# Battery_Management__rev3.net
KiCad netlist of a schematic drawn in Altium Designer
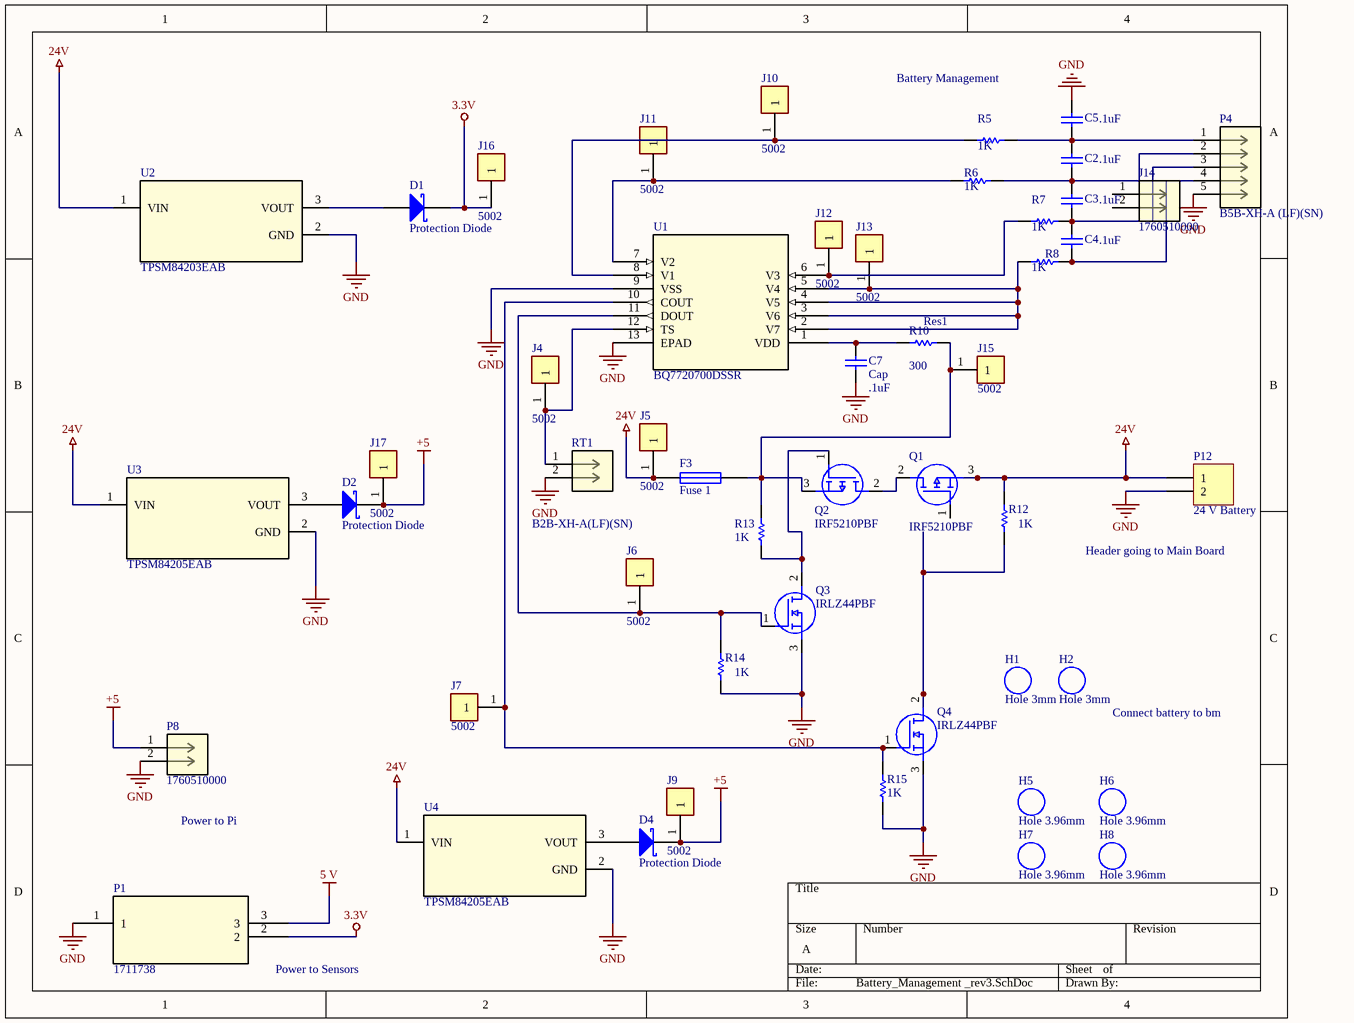
[diagram p0: Battery_Management _rev3.SchDoc]

(export (version "E")
  (design (tool "Eeschema 10.0.6"))
  (components
    (comp (ref "C2")
      (value ".1uF")
      (footprint "RAD-0.3")
      (description "Capacitor")
      (fields (field (name "Comment") "Cap") (field (name "PUBLISHER") "Altium Limited"))
      (libsource (lib "Miscellaneous Devices") (part "Cap"))
    )
    (comp (ref "C3")
      (value ".1uF")
      (footprint "RAD-0.3")
      (description "Capacitor")
      (fields (field (name "Comment") "Cap") (field (name "PUBLISHER") "Altium Limited"))
      (libsource (lib "Miscellaneous Devices") (part "Cap"))
    )
    (comp (ref "C4")
      (value ".1uF")
      (footprint "RAD-0.3")
      (description "Capacitor")
      (fields (field (name "Comment") "Cap") (field (name "PUBLISHER") "Altium Limited"))
      (libsource (lib "Miscellaneous Devices") (part "Cap"))
    )
    (comp (ref "C5")
      (value ".1uF")
      (footprint "RAD-0.3")
      (description "Capacitor")
      (fields (field (name "Comment") "Cap") (field (name "PUBLISHER") "Altium Limited"))
      (libsource (lib "Miscellaneous Devices") (part "Cap"))
    )
    (comp (ref "C7")
      (value "Cap")
      (footprint "RAD-0.3")
      (description "Capacitor")
      (fields (field (name "ALTIUM_VALUE") ".1uF") (field (name "PUBLISHER") "Altium Limited"))
      (libsource (lib "Miscellaneous Devices") (part "Cap"))
    )
    (comp (ref "D1")
      (value "Protection Diode")
      (footprint "TO-220AC")
      (description "Schottky Rectifier")
      (fields (field (name "PUBLISHER") "Altium Limited"))
      (libsource (lib "Miscellaneous Devices") (part "Diode 10TQ035"))
    )
    (comp (ref "D2")
      (value "Protection Diode")
      (footprint "TO-220AC")
      (description "Schottky Rectifier")
      (fields (field (name "PUBLISHER") "Altium Limited"))
      (libsource (lib "Miscellaneous Devices") (part "Diode 10TQ035"))
    )
    (comp (ref "D4")
      (value "Protection Diode")
      (footprint "TO-220AC")
      (description "Schottky Rectifier")
      (fields (field (name "PUBLISHER") "Altium Limited"))
      (libsource (lib "Miscellaneous Devices") (part "Diode 10TQ035"))
    )
    (comp (ref "F3")
      (value "Fuse 1")
      (footprint "PIN-W2/E2.8")
      (description "Fuse")
      (fields (field (name "PUBLISHER") "Altium Limited"))
      (libsource (lib "Miscellaneous Devices") (part "Fuse 1"))
    )
    (comp (ref "H1")
      (value "Hole 3mm")
      (footprint "Hole 3mm")
      (libsource (lib "ECE LIB 21") (part "Hole 3mm"))
    )
    (comp (ref "H2")
      (value "Hole 3mm")
      (footprint "Hole 3mm")
      (libsource (lib "ECE LIB 21") (part "Hole 3mm"))
    )
    (comp (ref "H5")
      (value "Hole 3.96mm")
      (footprint "Hole 3mm")
      (libsource (lib "ECE LIB 21") (part "Hole 3mm"))
    )
    (comp (ref "H6")
      (value "Hole 3.96mm")
      (footprint "Hole 3mm")
      (libsource (lib "ECE LIB 21") (part "Hole 3mm"))
    )
    (comp (ref "H7")
      (value "Hole 3.96mm")
      (footprint "Hole 3mm")
      (libsource (lib "ECE LIB 21") (part "Hole 3mm"))
    )
    (comp (ref "H8")
      (value "Hole 3.96mm")
      (footprint "Hole 3mm")
      (libsource (lib "ECE LIB 21") (part "Hole 3mm"))
    )
    (comp (ref "J4")
      (value "5002")
      (footprint "KEYSTONE_5002")
      (description "2.2ÂµH Shielded Wirewound Inductor 1.8A 66mOhm Max Nonstandard")
      (fields (field (name "MF") "Keystone Electronics"))
      (libsource (lib "") (part "5002_1"))
    )
    (comp (ref "J5")
      (value "5002")
      (footprint "KEYSTONE_5002")
      (description "2.2ÂµH Shielded Wirewound Inductor 1.8A 66mOhm Max Nonstandard")
      (fields (field (name "MF") "Keystone Electronics"))
      (libsource (lib "") (part "5002_1"))
    )
    (comp (ref "J6")
      (value "5002")
      (footprint "KEYSTONE_5002")
      (description "2.2ÂµH Shielded Wirewound Inductor 1.8A 66mOhm Max Nonstandard")
      (fields (field (name "MF") "Keystone Electronics"))
      (libsource (lib "") (part "5002_1"))
    )
    (comp (ref "J7")
      (value "5002")
      (footprint "KEYSTONE_5002")
      (description "2.2ÂµH Shielded Wirewound Inductor 1.8A 66mOhm Max Nonstandard")
      (fields (field (name "MF") "Keystone Electronics"))
      (libsource (lib "5002") (part "5002"))
    )
    (comp (ref "J9")
      (value "5002")
      (footprint "KEYSTONE_5002")
      (description "2.2ÂµH Shielded Wirewound Inductor 1.8A 66mOhm Max Nonstandard")
      (fields (field (name "MF") "Keystone Electronics"))
      (libsource (lib "") (part "5002_1"))
    )
    (comp (ref "J10")
      (value "5002")
      (footprint "KEYSTONE_5002")
      (description "2.2ÂµH Shielded Wirewound Inductor 1.8A 66mOhm Max Nonstandard")
      (fields (field (name "MF") "Keystone Electronics"))
      (libsource (lib "") (part "5002_1"))
    )
    (comp (ref "J11")
      (value "5002")
      (footprint "KEYSTONE_5002")
      (description "2.2ÂµH Shielded Wirewound Inductor 1.8A 66mOhm Max Nonstandard")
      (fields (field (name "MF") "Keystone Electronics"))
      (libsource (lib "") (part "5002_1"))
    )
    (comp (ref "J12")
      (value "5002")
      (footprint "KEYSTONE_5002")
      (description "2.2ÂµH Shielded Wirewound Inductor 1.8A 66mOhm Max Nonstandard")
      (fields (field (name "MF") "Keystone Electronics"))
      (libsource (lib "") (part "5002_1"))
    )
    (comp (ref "J13")
      (value "5002")
      (footprint "KEYSTONE_5002")
      (description "2.2ÂµH Shielded Wirewound Inductor 1.8A 66mOhm Max Nonstandard")
      (fields (field (name "MF") "Keystone Electronics"))
      (libsource (lib "") (part "5002_1"))
    )
    (comp (ref "J14")
      (value "1760510000")
      (footprint "CONN2_1760510000_WED")
      (description "No Description Available")
      (fields (field (name "COPYRIGHT") "Copyright (C) 2022 Ultra Librarian. All rights reserved."))
      (libsource (lib "1760510000") (part "1760510000"))
    )
    (comp (ref "J15")
      (value "5002")
      (footprint "KEYSTONE_5002")
      (description "2.2ÂµH Shielded Wirewound Inductor 1.8A 66mOhm Max Nonstandard")
      (fields (field (name "MF") "Keystone Electronics"))
      (libsource (lib "") (part "5002_2"))
    )
    (comp (ref "J16")
      (value "5002")
      (footprint "KEYSTONE_5002")
      (description "2.2ÂµH Shielded Wirewound Inductor 1.8A 66mOhm Max Nonstandard")
      (fields (field (name "MF") "Keystone Electronics"))
      (libsource (lib "") (part "5002_1"))
    )
    (comp (ref "J17")
      (value "5002")
      (footprint "KEYSTONE_5002")
      (description "2.2ÂµH Shielded Wirewound Inductor 1.8A 66mOhm Max Nonstandard")
      (fields (field (name "MF") "Keystone Electronics"))
      (libsource (lib "") (part "5002_1"))
    )
    (comp (ref "P1")
      (value "1711738")
      (footprint "1711738_PXC")
      (description "No Description Available")
      (fields (field (name "COPYRIGHT") "Copyright (C) 2022 Ultra Librarian. All rights reserved."))
      (libsource (lib "1711738") (part "1711738"))
    )
    (comp (ref "P4")
      (value "B5B-XH-A (LF)(SN)")
      (footprint "CONN_B5B-XH-A (LF)(SN)_JST")
      (description "No Description Available")
      (fields (field (name "COPYRIGHT") "Copyright (C) 2022 Ultra Librarian. All rights reserved."))
      (libsource (lib "B5B-XH-A_LF__SN_") (part "B5B-XH-A (LF)(SN)"))
    )
    (comp (ref "P8")
      (value "1760510000")
      (footprint "CONN2_1760510000_WED")
      (description "No Description Available")
      (fields (field (name "COPYRIGHT") "Copyright (C) 2022 Ultra Librarian. All rights reserved."))
      (libsource (lib "1760510000") (part "1760510000"))
    )
    (comp (ref "P12")
      (value "24 V Battery")
      (footprint "MHDR1X2")
      (description "Header, 2-Pin")
      (fields (field (name "PUBLISHER") "Altium Limited"))
      (libsource (lib "Miscellaneous Connectors") (part "MHDR1X2"))
    )
    (comp (ref "Q1")
      (value "IRF5210PBF")
      (footprint "TO254P469X1042X1967-3P")
      (fields (field (name "MOUSER PART NUMBER") "942-IRF5210PBF"))
      (libsource (lib "IRF5210PBF") (part "IRF5210PBF"))
    )
    (comp (ref "Q2")
      (value "IRF5210PBF")
      (footprint "TO254P469X1042X1967-3P")
      (fields (field (name "MOUSER PART NUMBER") "942-IRF5210PBF"))
      (libsource (lib "IRF5210PBF") (part "IRF5210PBF"))
    )
    (comp (ref "Q3")
      (value "IRLZ44PBF")
      (footprint "TO254P465X1024X2050-3P")
      (description "Trans MOSFET N-CH 60V 50A")
      (fields (field (name "MOUSER PART NUMBER") "844-IRLZ44PBF"))
      (libsource (lib "IRLZ44PBF") (part "IRLZ44PBF"))
    )
    (comp (ref "Q4")
      (value "IRLZ44PBF")
      (footprint "TO254P465X1024X2050-3P")
      (description "Trans MOSFET N-CH 60V 50A")
      (fields (field (name "MOUSER PART NUMBER") "844-IRLZ44PBF"))
      (libsource (lib "IRLZ44PBF") (part "IRLZ44PBF"))
    )
    (comp (ref "R5")
      (value "1K")
      (footprint "AXIAL-0.3")
      (description "Resistor")
      (fields (field (name "PUBLISHER") "Altium Limited"))
      (libsource (lib "Miscellaneous Devices") (part "Res1"))
    )
    (comp (ref "R6")
      (value "1K")
      (footprint "AXIAL-0.3")
      (description "Resistor")
      (fields (field (name "Comment") "Res1") (field (name "PUBLISHER") "Altium Limited"))
      (libsource (lib "Miscellaneous Devices") (part "Res1"))
    )
    (comp (ref "R7")
      (value "1K")
      (footprint "AXIAL-0.3")
      (description "Resistor")
      (fields (field (name "PUBLISHER") "Altium Limited"))
      (libsource (lib "Miscellaneous Devices") (part "Res1"))
    )
    (comp (ref "R8")
      (value "1K")
      (footprint "AXIAL-0.3")
      (description "Resistor")
      (fields (field (name "Comment") "Res1") (field (name "PUBLISHER") "Altium Limited"))
      (libsource (lib "Miscellaneous Devices") (part "Res1"))
    )
    (comp (ref "R10")
      (value "Res1")
      (footprint "AXIAL-0.3")
      (description "Resistor")
      (fields (field (name "ALTIUM_VALUE") "300") (field (name "PUBLISHER") "Altium Limited"))
      (libsource (lib "Miscellaneous Devices") (part "Res1"))
    )
    (comp (ref "R12")
      (value "1K")
      (footprint "AXIAL-0.3")
      (description "Resistor")
      (fields (field (name "Comment") "Res1") (field (name "PUBLISHER") "Altium Limited"))
      (libsource (lib "Miscellaneous Devices") (part "Res1"))
    )
    (comp (ref "R13")
      (value "1K")
      (footprint "AXIAL-0.3")
      (description "Resistor")
      (fields (field (name "Comment") "Res1") (field (name "PUBLISHER") "Altium Limited"))
      (libsource (lib "Miscellaneous Devices") (part "Res1"))
    )
    (comp (ref "R14")
      (value "1K")
      (footprint "AXIAL-0.3")
      (description "Resistor")
      (fields (field (name "Comment") "Res1") (field (name "PUBLISHER") "Altium Limited"))
      (libsource (lib "Miscellaneous Devices") (part "Res1"))
    )
    (comp (ref "R15")
      (value "1K")
      (footprint "AXIAL-0.3")
      (description "Resistor")
      (fields (field (name "Comment") "Res1") (field (name "PUBLISHER") "Altium Limited"))
      (libsource (lib "Miscellaneous Devices") (part "Res1"))
    )
    (comp (ref "RT1")
      (value "B2B-XH-A(LF)(SN)")
      (footprint "CONN_B2B-XH-A(LF)(SN)_JST")
      (description "fOR RT")
      (fields (field (name "COPYRIGHT") "Copyright (C) 2022 Ultra Librarian. All rights reserved."))
      (libsource (lib "B2B-XH-A_LF__SN_") (part "B2B-XH-A(LF)(SN)"))
    )
    (comp (ref "U1")
      (value "BQ7720700DSSR")
      (footprint "WSON12_DSS_TEX")
      (description "No Description Available")
      (fields (field (name "COPYRIGHT") "Copyright (C) 2022 Ultra Librarian. All rights reserved."))
      (libsource (lib "BQ7720700DSSR") (part "BQ7720700DSSR"))
    )
    (comp (ref "U2")
      (value "TPSM84203EAB")
      (footprint "EAB0003A")
      (description "No Description Available")
      (fields (field (name "COPYRIGHT") "Copyright (C) 2022 Ultra Librarian. All rights reserved."))
      (libsource (lib "TPSM84203EAB") (part "TPSM84203EAB"))
    )
    (comp (ref "U3")
      (value "TPSM84205EAB")
      (footprint "EAB0003A")
      (description "No Description Available")
      (fields (field (name "COPYRIGHT") "Copyright (C) 2022 Ultra Librarian. All rights reserved."))
      (libsource (lib "TPSM84205EAB") (part "TPSM84205EAB_1"))
    )
    (comp (ref "U4")
      (value "TPSM84205EAB")
      (footprint "EAB0003A")
      (description "No Description Available")
      (fields (field (name "COPYRIGHT") "Copyright (C) 2022 Ultra Librarian. All rights reserved."))
      (libsource (lib "TPSM84205EAB") (part "TPSM84205EAB_1"))
    )
  )
  (nets
    (net (code "1") (name "+5") (class "Default")
      (node (ref "D2") (pin "1") (pinfunction "K_1") (pintype "passive"))
      (node (ref "D4") (pin "1") (pinfunction "K_1") (pintype "passive"))
      (node (ref "J17") (pin "1") (pinfunction "1_1") (pintype "passive"))
      (node (ref "J9") (pin "1") (pinfunction "1_1") (pintype "passive"))
      (node (ref "P8") (pin "1") (pinfunction "1_1") (pintype "passive"))
    )
    (net (code "2") (name "3.3V") (class "Default")
      (node (ref "D1") (pin "1") (pinfunction "K_1") (pintype "passive"))
      (node (ref "J16") (pin "1") (pinfunction "1_1") (pintype "passive"))
      (node (ref "P1") (pin "2") (pinfunction "2_2") (pintype "passive"))
    )
    (net (code "3") (name "5 V") (class "Default")
      (node (ref "P1") (pin "3") (pinfunction "3_3") (pintype "passive"))
    )
    (net (code "4") (name "24V") (class "Default")
      (node (ref "F3") (pin "2") (pinfunction "2_2") (pintype "passive"))
      (node (ref "J5") (pin "1") (pinfunction "1_1") (pintype "passive"))
      (node (ref "P12") (pin "1") (pinfunction "1_1") (pintype "passive"))
      (node (ref "Q1") (pin "3") (pinfunction "S_3") (pintype "passive"))
      (node (ref "R12") (pin "2") (pinfunction "2_2") (pintype "passive"))
      (node (ref "U2") (pin "1") (pinfunction "VIN_1") (pintype "power_in"))
      (node (ref "U3") (pin "1") (pinfunction "VIN_1") (pintype "power_in"))
      (node (ref "U4") (pin "1") (pinfunction "VIN_1") (pintype "power_in"))
    )
    (net (code "5") (name "GND") (class "Default")
      (node (ref "C5") (pin "2") (pinfunction "2_2") (pintype "passive"))
      (node (ref "C7") (pin "1") (pinfunction "1_1") (pintype "passive"))
      (node (ref "P1") (pin "1") (pinfunction "1_1") (pintype "passive"))
      (node (ref "P12") (pin "2") (pinfunction "2_2") (pintype "passive"))
      (node (ref "P4") (pin "5") (pinfunction "5_5") (pintype "passive"))
      (node (ref "P8") (pin "2") (pinfunction "2_2") (pintype "passive"))
      (node (ref "Q3") (pin "3") (pinfunction "S_3") (pintype "passive"))
      (node (ref "Q4") (pin "3") (pinfunction "S_3") (pintype "passive"))
      (node (ref "R14") (pin "1") (pinfunction "1_1") (pintype "passive"))
      (node (ref "R15") (pin "1") (pinfunction "1_1") (pintype "passive"))
      (node (ref "RT1") (pin "2") (pinfunction "2_2") (pintype "passive"))
      (node (ref "U1") (pin "13") (pinfunction "EPAD_13") (pintype "passive"))
      (node (ref "U1") (pin "9") (pinfunction "VSS_9") (pintype "passive"))
      (node (ref "U2") (pin "2") (pinfunction "GND_2") (pintype "power_in"))
      (node (ref "U3") (pin "2") (pinfunction "GND_2") (pintype "power_in"))
      (node (ref "U4") (pin "2") (pinfunction "GND_2") (pintype "power_in"))
    )
    (net (code "6") (name "Net-(C2-Pad1)") (class "Default")
      (node (ref "C2") (pin "1") (pinfunction "1_1") (pintype "passive"))
      (node (ref "C3") (pin "2") (pinfunction "2_2") (pintype "passive"))
      (node (ref "P4") (pin "2") (pinfunction "2_2") (pintype "passive"))
      (node (ref "R6") (pin "2") (pinfunction "2_2") (pintype "passive"))
    )
    (net (code "7") (name "Net-(C2-Pad2)") (class "Default")
      (node (ref "C2") (pin "2") (pinfunction "2_2") (pintype "passive"))
      (node (ref "C5") (pin "1") (pinfunction "1_1") (pintype "passive"))
      (node (ref "P4") (pin "1") (pinfunction "1_1") (pintype "passive"))
      (node (ref "R5") (pin "2") (pinfunction "2_2") (pintype "passive"))
    )
    (net (code "8") (name "Net-(C3-Pad1)") (class "Default")
      (node (ref "C3") (pin "1") (pinfunction "1_1") (pintype "passive"))
      (node (ref "C4") (pin "2") (pinfunction "2_2") (pintype "passive"))
      (node (ref "P4") (pin "3") (pinfunction "3_3") (pintype "passive"))
      (node (ref "R7") (pin "2") (pinfunction "2_2") (pintype "passive"))
    )
    (net (code "9") (name "Net-(C4-Pad1)") (class "Default")
      (node (ref "C4") (pin "1") (pinfunction "1_1") (pintype "passive"))
      (node (ref "P4") (pin "4") (pinfunction "4_4") (pintype "passive"))
      (node (ref "R8") (pin "2") (pinfunction "2_2") (pintype "passive"))
    )
    (net (code "10") (name "Net-(D1-A)") (class "Default")
      (node (ref "D1") (pin "3") (pinfunction "A_3") (pintype "passive"))
      (node (ref "U2") (pin "3") (pinfunction "VOUT_3") (pintype "power_in"))
    )
    (net (code "11") (name "Net-(D2-A)") (class "Default")
      (node (ref "D2") (pin "3") (pinfunction "A_3") (pintype "passive"))
      (node (ref "U3") (pin "3") (pinfunction "VOUT_3") (pintype "power_in"))
    )
    (net (code "12") (name "Net-(D4-A)") (class "Default")
      (node (ref "D4") (pin "3") (pinfunction "A_3") (pintype "passive"))
      (node (ref "U4") (pin "3") (pinfunction "VOUT_3") (pintype "power_in"))
    )
    (net (code "13") (name "Net-(Q1-D)") (class "Default")
      (node (ref "Q1") (pin "2") (pinfunction "D_2") (pintype "passive"))
      (node (ref "Q2") (pin "2") (pinfunction "D_2") (pintype "passive"))
    )
    (net (code "14") (name "Net-(Q2-G)") (class "Default")
      (node (ref "Q2") (pin "1") (pinfunction "G_1") (pintype "passive"))
      (node (ref "Q3") (pin "2") (pinfunction "D_2") (pintype "passive"))
      (node (ref "R13") (pin "1") (pinfunction "1_1") (pintype "passive"))
    )
    (net (code "15") (name "Net-(Q2-S)") (class "Default")
      (node (ref "F3") (pin "1") (pinfunction "1_1") (pintype "passive"))
      (node (ref "J15") (pin "1") (pinfunction "1_1") (pintype "passive"))
      (node (ref "Q2") (pin "3") (pinfunction "S_3") (pintype "passive"))
      (node (ref "R10") (pin "2") (pinfunction "2_2") (pintype "passive"))
      (node (ref "R13") (pin "2") (pinfunction "2_2") (pintype "passive"))
    )
    (net (code "16") (name "Net-(Q3-G)") (class "Default")
      (node (ref "J6") (pin "1") (pinfunction "1_1") (pintype "passive"))
      (node (ref "Q3") (pin "1") (pinfunction "G_1") (pintype "passive"))
      (node (ref "R14") (pin "2") (pinfunction "2_2") (pintype "passive"))
      (node (ref "U1") (pin "11") (pinfunction "DOUT_11") (pintype "output"))
    )
    (net (code "17") (name "Net-(Q4-D)") (class "Default")
      (node (ref "Q4") (pin "2") (pinfunction "D_2") (pintype "passive"))
      (node (ref "R12") (pin "1") (pinfunction "1_1") (pintype "passive"))
    )
    (net (code "18") (name "Net-(Q4-G)") (class "Default")
      (node (ref "J7") (pin "1") (pinfunction "1_1") (pintype "passive"))
      (node (ref "Q4") (pin "1") (pinfunction "G_1") (pintype "passive"))
      (node (ref "R15") (pin "2") (pinfunction "2_2") (pintype "passive"))
      (node (ref "U1") (pin "10") (pinfunction "COUT_10") (pintype "output"))
    )
    (net (code "19") (name "Net-(U1-TS)") (class "Default")
      (node (ref "J4") (pin "1") (pinfunction "1_1") (pintype "passive"))
      (node (ref "RT1") (pin "1") (pinfunction "1_1") (pintype "passive"))
      (node (ref "U1") (pin "12") (pinfunction "TS_12") (pintype "input"))
    )
    (net (code "20") (name "Net-(U1-V1)") (class "Default")
      (node (ref "J10") (pin "1") (pinfunction "1_1") (pintype "passive"))
      (node (ref "R5") (pin "1") (pinfunction "1_1") (pintype "passive"))
      (node (ref "U1") (pin "8") (pinfunction "V1_8") (pintype "input"))
    )
    (net (code "21") (name "Net-(U1-V2)") (class "Default")
      (node (ref "J11") (pin "1") (pinfunction "1_1") (pintype "passive"))
      (node (ref "R6") (pin "1") (pinfunction "1_1") (pintype "passive"))
      (node (ref "U1") (pin "7") (pinfunction "V2_7") (pintype "input"))
    )
    (net (code "22") (name "Net-(U1-V3)") (class "Default")
      (node (ref "J12") (pin "1") (pinfunction "1_1") (pintype "passive"))
      (node (ref "R7") (pin "1") (pinfunction "1_1") (pintype "passive"))
      (node (ref "U1") (pin "6") (pinfunction "V3_6") (pintype "input"))
    )
    (net (code "23") (name "Net-(U1-V4)") (class "Default")
      (node (ref "J13") (pin "1") (pinfunction "1_1") (pintype "passive"))
      (node (ref "R8") (pin "1") (pinfunction "1_1") (pintype "passive"))
      (node (ref "U1") (pin "2") (pinfunction "V7_2") (pintype "input"))
      (node (ref "U1") (pin "3") (pinfunction "V6_3") (pintype "input"))
      (node (ref "U1") (pin "4") (pinfunction "V5_4") (pintype "input"))
      (node (ref "U1") (pin "5") (pinfunction "V4_5") (pintype "input"))
    )
    (net (code "24") (name "Net-(U1-VDD)") (class "Default")
      (node (ref "C7") (pin "2") (pinfunction "2_2") (pintype "passive"))
      (node (ref "R10") (pin "1") (pinfunction "1_1") (pintype "passive"))
      (node (ref "U1") (pin "1") (pinfunction "VDD_1") (pintype "power_in"))
    )
    (net (code "25") (name "unconnected-(J14-Pad1)") (class "Default")
      (node (ref "J14") (pin "1") (pinfunction "1_1") (pintype "passive"))
    )
    (net (code "26") (name "unconnected-(J14-Pad2)") (class "Default")
      (node (ref "J14") (pin "2") (pinfunction "2_2") (pintype "passive"))
    )
    (net (code "27") (name "unconnected-(Q1-G-Pad1)") (class "Default")
      (node (ref "Q1") (pin "1") (pinfunction "G_1") (pintype "passive"))
    )
  )
)
